# Power.net
KiCad netlist of a schematic drawn in Altium Designer
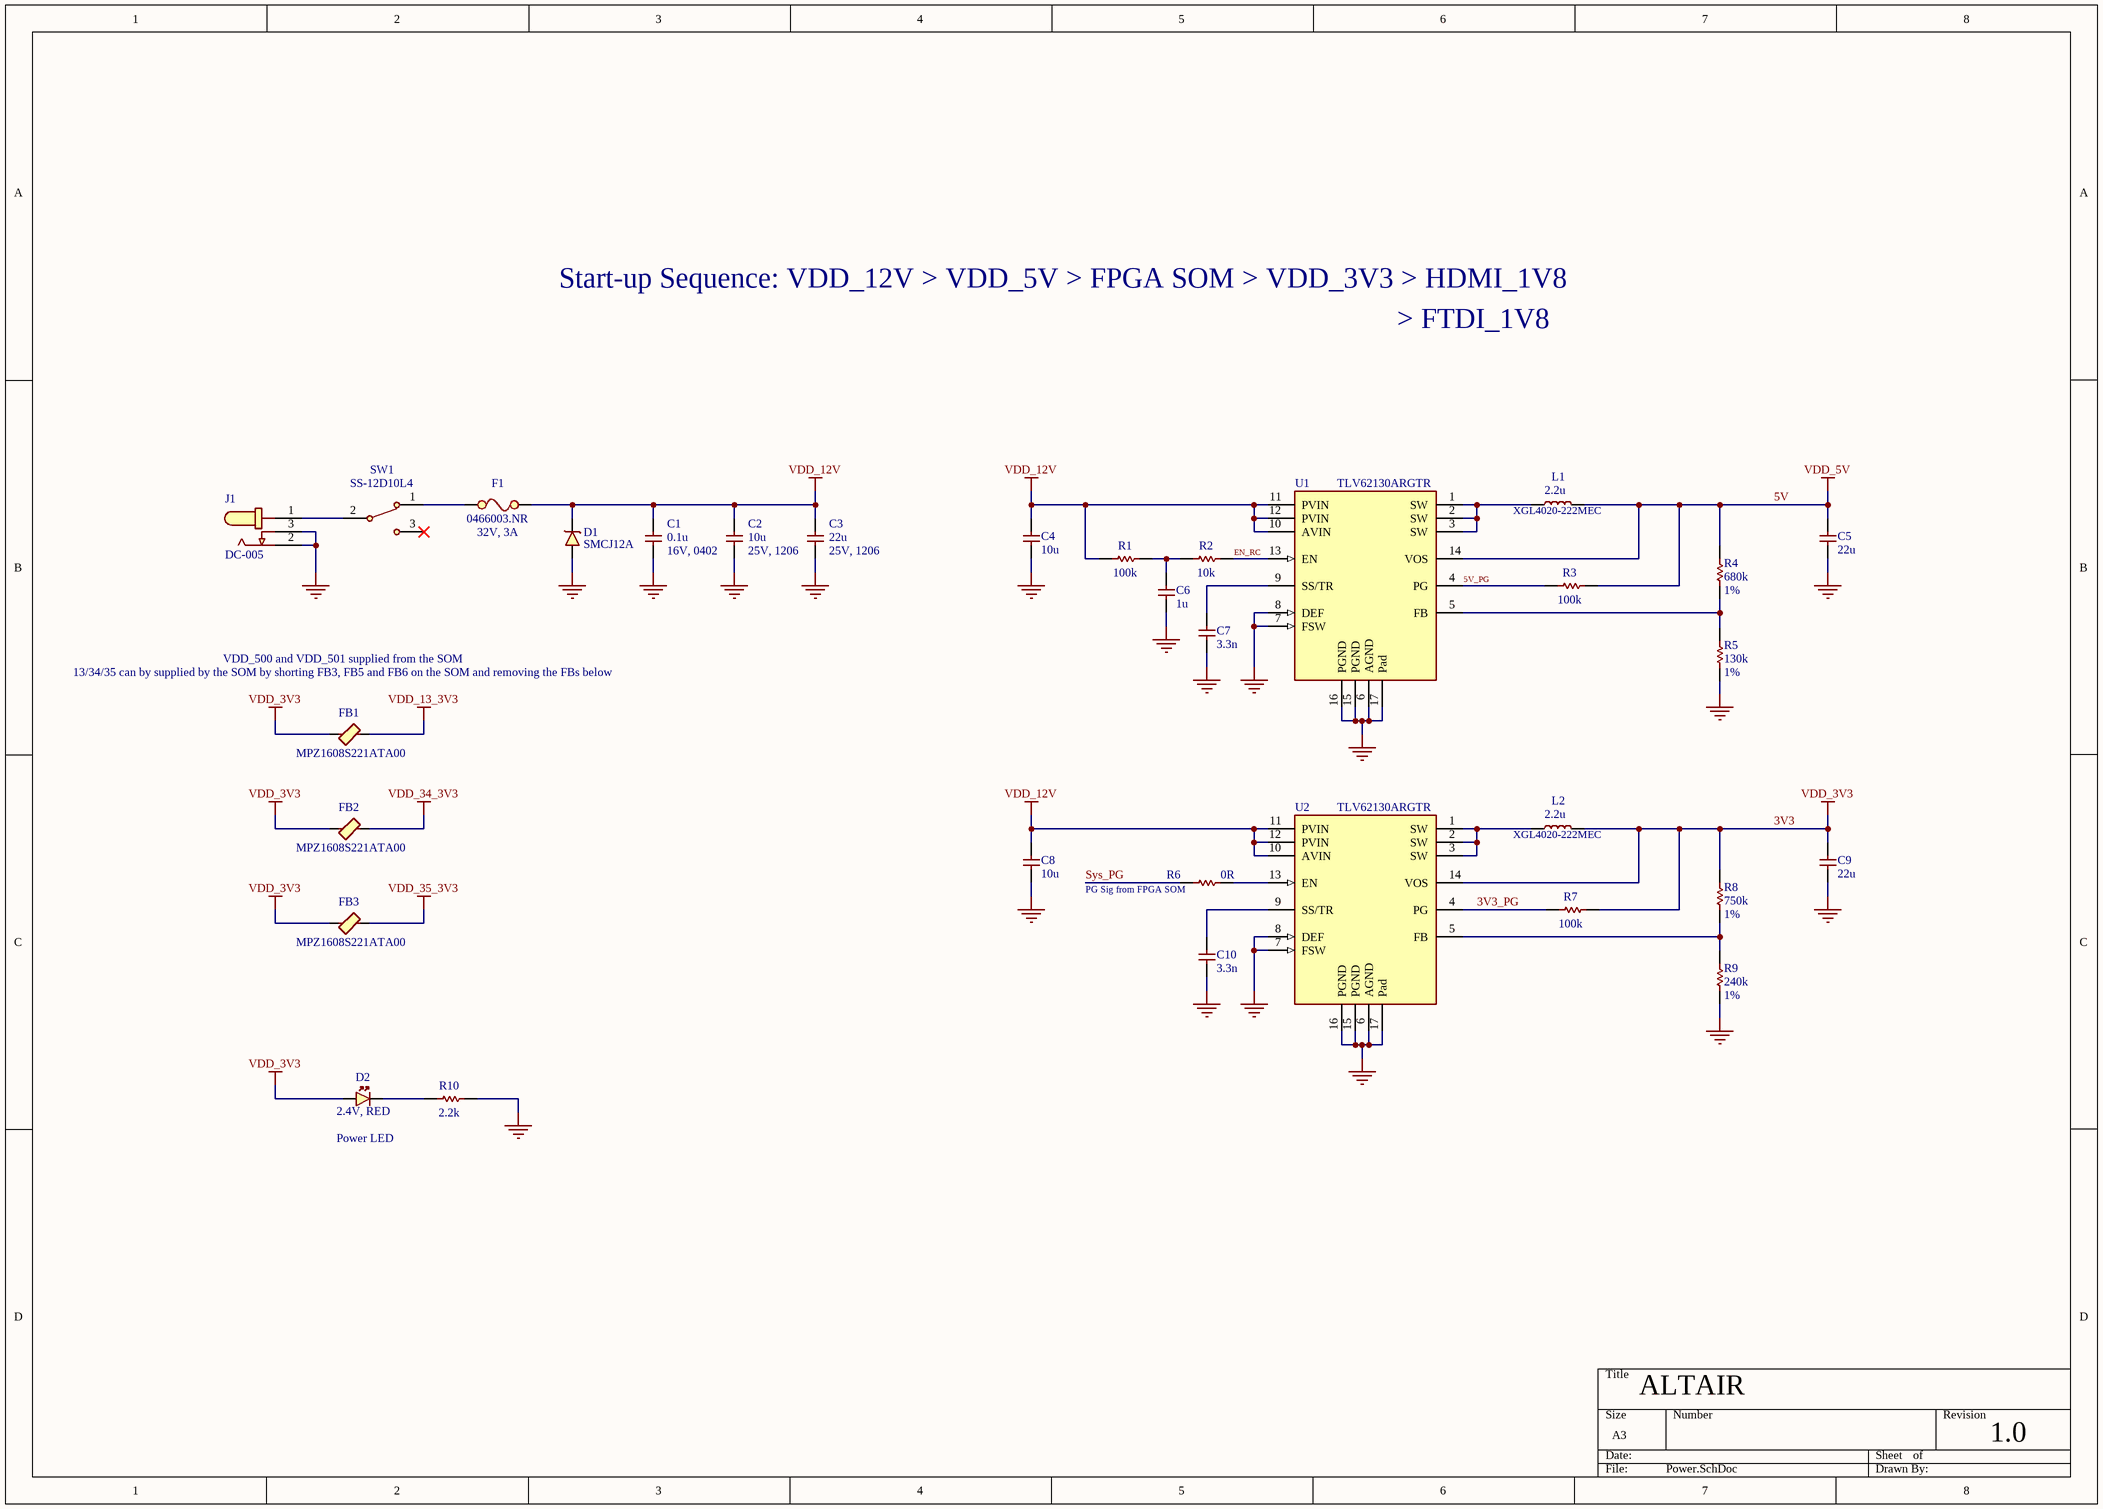
[diagram p0: Power.SchDoc]

(export (version "E")
  (design (tool "Eeschema 10.0.6"))
  (components
    (comp (ref "C1")
      (value "0.1u")
      (footprint "CAP_0402")
      (description "Capacitor SMD 0402")
      (fields
        (field (name "NOTE/MISC") "16V, 0402")
        (field (name "PART NO") "CL05B104KO5NNNC")
        (field (name "JLCPCB PART #") "C338112")
      )
      (libsource (lib "personalGenericLib") (part "CAP_0402"))
    )
    (comp (ref "C2")
      (value "10u")
      (footprint "CAP_1206")
      (description "Capacitor SMD 1206")
      (fields
        (field (name "NOTE/MISC") "25V, 1206")
        (field (name "PART NO") "CL31A106KAHNNNE")
        (field (name "JLCPCB PART #") "C9807")
      )
      (libsource (lib "personalGenericLib") (part "CAP_1206"))
    )
    (comp (ref "C3")
      (value "22u")
      (footprint "CAP_1206")
      (description "Capacitor SMD 1206")
      (fields
        (field (name "NOTE/MISC") "25V, 1206")
        (field (name "PART NO") "CL31A226KAHNNNE")
        (field (name "JLCPCB PART #") "C12891")
      )
      (libsource (lib "personalGenericLib") (part "CAP_1206"))
    )
    (comp (ref "C4")
      (value "10u")
      (footprint "CAP_1206")
      (description "Capacitor SMD 1206")
      (fields (field (name "PART NO") "CL31A106KAHNNNE") (field (name "JLCPCB PART #") "C9807"))
      (libsource (lib "personalGenericLib") (part "CAP_1206"))
    )
    (comp (ref "C5")
      (value "22u")
      (footprint "CAP_1206")
      (description "Capacitor SMD 1206")
      (fields (field (name "PART NO") "CL31A226KAHNNNE") (field (name "JLCPCB PART #") "C12891"))
      (libsource (lib "personalGenericLib") (part "CAP_1206"))
    )
    (comp (ref "C6")
      (value "1u")
      (footprint "CAP_0402")
      (description "Capacitor SMD 0402")
      (fields (field (name "JLCPCB PART #") "C14445") (field (name "PART NO") "CL05A105KP5NNNC"))
      (libsource (lib "personalGenericLib") (part "CAP_0402"))
    )
    (comp (ref "C7")
      (value "3.3n")
      (footprint "CAP_0402")
      (description "Capacitor SMD 0402")
      (fields (field (name "JLCPCB PART #") "C527004") (field (name "PART NO") "CC0402JRX7R8BB332"))
      (libsource (lib "personalGenericLib") (part "CAP_0402"))
    )
    (comp (ref "C8")
      (value "10u")
      (footprint "CAP_1206")
      (description "Capacitor SMD 1206")
      (fields (field (name "PART NO") "CL31A106KAHNNNE") (field (name "JLCPCB PART #") "C9807"))
      (libsource (lib "personalGenericLib") (part "CAP_1206"))
    )
    (comp (ref "C9")
      (value "22u")
      (footprint "CAP_1206")
      (description "Capacitor SMD 1206")
      (fields (field (name "PART NO") "CL31A226KAHNNNE") (field (name "JLCPCB PART #") "C12891"))
      (libsource (lib "personalGenericLib") (part "CAP_1206"))
    )
    (comp (ref "C10")
      (value "3.3n")
      (footprint "CAP_0402")
      (description "Capacitor SMD 0402")
      (fields (field (name "JLCPCB PART #") "C527004") (field (name "PART NO") "CC0402JRX7R8BB332"))
      (libsource (lib "personalGenericLib") (part "CAP_0402"))
    )
    (comp (ref "D1")
      (value "SMCJ12A")
      (footprint "LFUS-DO-214AB-2_V")
      (fields (field (name "JLCPCB PART #") "C224038"))
      (libsource (lib "personalGenericLib") (part "SMCJ12A"))
    )
    (comp (ref "D2")
      (value "RED")
      (footprint "LED_0805_RED")
      (description "LED 0805 RED SMD")
      (fields
        (field (name "JLCPCB PART #") "C497952")
        (field (name "NOTE/MISC") "2.4V, RED")
        (field (name "PART NO") "HL-PSC-2012S9AC")
      )
      (libsource (lib "personalGenericLib") (part "LED_0805_RED"))
    )
    (comp (ref "F1")
      (value "0466003.NR")
      (footprint "0466003.NR")
      (description "FUSE MNT 3A 32VAC/VDC 1206")
      (fields (field (name "JLCPCB PART #") "C14165") (field (name "NOTE/MISC") "32V, 3A"))
      (libsource (lib "personalGenericLib") (part "0466003.NR"))
    )
    (comp (ref "FB1")
      (value "220")
      (footprint "BEADC1608X75N")
      (description "Ferrite Bead")
      (fields (field (name "PART NO") "MPZ1608S221ATA00") (field (name "JLCPCB PART #") "C76815"))
      (libsource (lib "personalGenericLib") (part "MPZ1608S221ATA00"))
    )
    (comp (ref "FB2")
      (value "220")
      (footprint "BEADC1608X75N")
      (description "Ferrite Bead")
      (fields (field (name "PART NO") "MPZ1608S221ATA00") (field (name "JLCPCB PART #") "C76815"))
      (libsource (lib "personalGenericLib") (part "MPZ1608S221ATA00"))
    )
    (comp (ref "FB3")
      (value "220")
      (footprint "BEADC1608X75N")
      (description "Ferrite Bead")
      (fields (field (name "PART NO") "MPZ1608S221ATA00") (field (name "JLCPCB PART #") "C76815"))
      (libsource (lib "personalGenericLib") (part "MPZ1608S221ATA00"))
    )
    (comp (ref "J1")
      (value "DC-005")
      (footprint "DC-005-A200")
      (description "DC Jack")
      (fields (field (name "JLCPCB PART #") "C720557"))
      (libsource (lib "personalGenericLib") (part "DC-005"))
    )
    (comp (ref "L1")
      (value "2.2u")
      (footprint "personalGenericFootprintLib:XGL4020222MEC")
      (description "Inductor SMD 2.2 uH")
      (fields
        (field (name "NOTE/MISC") "XGL4020-222MEC")
        (field (name "PART NO") "XGL4020-222MEC")
        (field (name "JLCPCB PART #") "C6012410")
      )
      (libsource (lib "personalGenericLib") (part "IND_XGL4020-222MEC"))
    )
    (comp (ref "L2")
      (value "2.2u")
      (footprint "personalGenericFootprintLib:XGL4020222MEC")
      (description "Inductor SMD 2.2 uH")
      (fields
        (field (name "NOTE/MISC") "XGL4020-222MEC")
        (field (name "PART NO") "XGL4020-222MEC")
        (field (name "JLCPCB PART #") "C6012410")
      )
      (libsource (lib "personalGenericLib") (part "IND_XGL4020-222MEC"))
    )
    (comp (ref "R1")
      (value "100k")
      (footprint "RES_0402")
      (description "Resistor SMD 0402")
      (fields (field (name "JLCPCB PART #") "C106234") (field (name "PART NO") "RC0402JR-07100KL"))
      (libsource (lib "personalGenericLib") (part "RES_0402"))
    )
    (comp (ref "R2")
      (value "10k")
      (footprint "RES_0402")
      (description "Resistor SMD 0402")
      (fields (field (name "JLCPCB PART #") "C60489") (field (name "PART NO") "RC0402JR-0710KL"))
      (libsource (lib "personalGenericLib") (part "RES_0402"))
    )
    (comp (ref "R3")
      (value "100k")
      (footprint "RES_0402")
      (description "Resistor SMD 0402")
      (fields (field (name "JLCPCB PART #") "C106234") (field (name "PART NO") "RC0402JR-07100KL"))
      (libsource (lib "personalGenericLib") (part "RES_0402"))
    )
    (comp (ref "R4")
      (value "680k")
      (footprint "RES_0402")
      (description "Resistor SMD 0402")
      (fields
        (field (name "JLCPCB PART #") "C163456")
        (field (name "NOTE/MISC") "1%")
        (field (name "PART NO") "RC0402FR-07680KL")
      )
      (libsource (lib "personalGenericLib") (part "RES_0402"))
    )
    (comp (ref "R5")
      (value "130k")
      (footprint "RES_0402")
      (description "Resistor SMD 0402")
      (fields
        (field (name "JLCPCB PART #") "C93946")
        (field (name "NOTE/MISC") "1%")
        (field (name "PART NO") "RC0402FR-07130KL")
      )
      (libsource (lib "personalGenericLib") (part "RES_0402"))
    )
    (comp (ref "R6")
      (value "0R")
      (footprint "RES_0402")
      (description "Resistor SMD 0402")
      (fields (field (name "JLCPCB PART #") "C60485") (field (name "PART NO") "RC0402JR-070RL"))
      (libsource (lib "personalGenericLib") (part "RES_0402"))
    )
    (comp (ref "R7")
      (value "100k")
      (footprint "RES_0402")
      (description "Resistor SMD 0402")
      (fields (field (name "JLCPCB PART #") "C106234") (field (name "PART NO") "RC0402JR-07100KL"))
      (libsource (lib "personalGenericLib") (part "RES_0402"))
    )
    (comp (ref "R8")
      (value "750k")
      (footprint "RES_0402")
      (description "Resistor SMD 0402")
      (fields
        (field (name "JLCPCB PART #") "C137937")
        (field (name "NOTE/MISC") "1%")
        (field (name "PART NO") "RC0402FR-07750KL")
      )
      (libsource (lib "personalGenericLib") (part "RES_0402"))
    )
    (comp (ref "R9")
      (value "240k")
      (footprint "RES_0402")
      (description "Resistor SMD 0402")
      (fields
        (field (name "JLCPCB PART #") "C138029")
        (field (name "NOTE/MISC") "1%")
        (field (name "PART NO") "RC0402FR-07240KL")
      )
      (libsource (lib "personalGenericLib") (part "RES_0402"))
    )
    (comp (ref "R10")
      (value "2.2k")
      (footprint "RES_0402")
      (description "Resistor SMD 0402")
      (fields (field (name "JLCPCB PART #") "C163447") (field (name "PART NO") "RC0402JR-072K2L"))
      (libsource (lib "personalGenericLib") (part "RES_0402"))
    )
    (comp (ref "SW1")
      (value "SS-12D10L4")
      (footprint "SS-12D10L5")
      (description "Slide Switch")
      (fields (field (name "JLCPCB PART #") "C843364"))
      (libsource (lib "personalGenericLib") (part "SS-12D10L5"))
    )
    (comp (ref "U1")
      (value "TLV62130ARGTR")
      (footprint "FP-RGT0016C-MFG")
      (description "IC REG BUCK ADJUSTABLE 3A 16QFN")
      (fields (field (name "JLCPCB PART #") "C138520"))
      (libsource (lib "personalGenericLib") (part "TLV62130ARGTR"))
    )
    (comp (ref "U2")
      (value "TLV62130ARGTR")
      (footprint "FP-RGT0016C-MFG")
      (description "IC REG BUCK ADJUSTABLE 3A 16QFN")
      (fields (field (name "JLCPCB PART #") "C138520"))
      (libsource (lib "personalGenericLib") (part "TLV62130ARGTR"))
    )
  )
  (nets
    (net (code "1") (name "/3V3_PG") (class "Default")
      (node (ref "R7") (pin "1") (pinfunction "1_1") (pintype "passive"))
      (node (ref "U2") (pin "4") (pinfunction "PG_4") (pintype "open_collector"))
    )
    (net (code "2") (name "/5V_PG") (class "Default")
      (node (ref "R3") (pin "1") (pinfunction "1_1") (pintype "passive"))
      (node (ref "U1") (pin "4") (pinfunction "PG_4") (pintype "open_collector"))
    )
    (net (code "3") (name "/EN_RC") (class "Default")
      (node (ref "R2") (pin "1") (pinfunction "1_1") (pintype "passive"))
      (node (ref "U1") (pin "13") (pinfunction "EN_13") (pintype "input"))
    )
    (net (code "4") (name "/Sys_PG") (class "Default")
      (node (ref "R6") (pin "1") (pinfunction "1_1") (pintype "passive"))
    )
    (net (code "5") (name "GND") (class "Default")
      (node (ref "C1") (pin "1") (pinfunction "1_1") (pintype "passive"))
      (node (ref "C10") (pin "1") (pinfunction "1_1") (pintype "passive"))
      (node (ref "C2") (pin "1") (pinfunction "1_1") (pintype "passive"))
      (node (ref "C3") (pin "1") (pinfunction "1_1") (pintype "passive"))
      (node (ref "C4") (pin "1") (pinfunction "1_1") (pintype "passive"))
      (node (ref "C5") (pin "1") (pinfunction "1_1") (pintype "passive"))
      (node (ref "C6") (pin "1") (pinfunction "1_1") (pintype "passive"))
      (node (ref "C7") (pin "1") (pinfunction "1_1") (pintype "passive"))
      (node (ref "C8") (pin "1") (pinfunction "1_1") (pintype "passive"))
      (node (ref "C9") (pin "1") (pinfunction "1_1") (pintype "passive"))
      (node (ref "D1") (pin "2") (pinfunction "2_2") (pintype "passive"))
      (node (ref "J1") (pin "2") (pinfunction "2_2") (pintype "passive"))
      (node (ref "J1") (pin "3") (pinfunction "3_3") (pintype "passive"))
      (node (ref "R10") (pin "2") (pinfunction "2_2") (pintype "passive"))
      (node (ref "R5") (pin "2") (pinfunction "2_2") (pintype "passive"))
      (node (ref "R9") (pin "2") (pinfunction "2_2") (pintype "passive"))
      (node (ref "U1") (pin "15") (pinfunction "PGND_15") (pintype "power_in"))
      (node (ref "U1") (pin "16") (pinfunction "PGND_16") (pintype "power_in"))
      (node (ref "U1") (pin "17") (pinfunction "Pad_17") (pintype "power_in"))
      (node (ref "U1") (pin "6") (pinfunction "AGND_6") (pintype "power_in"))
      (node (ref "U1") (pin "7") (pinfunction "FSW_7") (pintype "input"))
      (node (ref "U1") (pin "8") (pinfunction "DEF_8") (pintype "input"))
      (node (ref "U2") (pin "15") (pinfunction "PGND_15") (pintype "power_in"))
      (node (ref "U2") (pin "16") (pinfunction "PGND_16") (pintype "power_in"))
      (node (ref "U2") (pin "17") (pinfunction "Pad_17") (pintype "power_in"))
      (node (ref "U2") (pin "6") (pinfunction "AGND_6") (pintype "power_in"))
      (node (ref "U2") (pin "7") (pinfunction "FSW_7") (pintype "input"))
      (node (ref "U2") (pin "8") (pinfunction "DEF_8") (pintype "input"))
    )
    (net (code "6") (name "Net-(C6-Pad2)") (class "Default")
      (node (ref "C6") (pin "2") (pinfunction "2_2") (pintype "passive"))
      (node (ref "R1") (pin "1") (pinfunction "1_1") (pintype "passive"))
      (node (ref "R2") (pin "2") (pinfunction "2_2") (pintype "passive"))
    )
    (net (code "7") (name "Net-(D2-PadK)") (class "Default")
      (node (ref "D2") (pin "K") (pinfunction "K_K") (pintype "passive"))
      (node (ref "R10") (pin "1") (pinfunction "1_1") (pintype "passive"))
    )
    (net (code "8") (name "Net-(F1-Pad1)") (class "Default")
      (node (ref "F1") (pin "1") (pinfunction "1_1") (pintype "passive"))
      (node (ref "SW1") (pin "1") (pinfunction "1_1") (pintype "passive"))
    )
    (net (code "9") (name "Net-(L1-Pad1)") (class "Default")
      (node (ref "L1") (pin "1") (pinfunction "1_1") (pintype "passive"))
      (node (ref "U1") (pin "1") (pinfunction "SW_1") (pintype "passive"))
      (node (ref "U1") (pin "2") (pinfunction "SW_2") (pintype "passive"))
      (node (ref "U1") (pin "3") (pinfunction "SW_3") (pintype "passive"))
    )
    (net (code "10") (name "Net-(L2-Pad1)") (class "Default")
      (node (ref "L2") (pin "1") (pinfunction "1_1") (pintype "passive"))
      (node (ref "U2") (pin "1") (pinfunction "SW_1") (pintype "passive"))
      (node (ref "U2") (pin "2") (pinfunction "SW_2") (pintype "passive"))
      (node (ref "U2") (pin "3") (pinfunction "SW_3") (pintype "passive"))
    )
    (net (code "11") (name "Net-(SW1-C)") (class "Default")
      (node (ref "J1") (pin "1") (pinfunction "1_1") (pintype "passive"))
      (node (ref "SW1") (pin "2") (pinfunction "C_2") (pintype "passive"))
    )
    (net (code "12") (name "Net-(U1-FB)") (class "Default")
      (node (ref "R4") (pin "1") (pinfunction "1_1") (pintype "passive"))
      (node (ref "R5") (pin "1") (pinfunction "1_1") (pintype "passive"))
      (node (ref "U1") (pin "5") (pinfunction "FB_5") (pintype "passive"))
    )
    (net (code "13") (name "Net-(U1-SS{slash}TR)") (class "Default")
      (node (ref "C7") (pin "2") (pinfunction "2_2") (pintype "passive"))
      (node (ref "U1") (pin "9") (pinfunction "SS/TR_9") (pintype "passive"))
    )
    (net (code "14") (name "Net-(U2-EN)") (class "Default")
      (node (ref "R6") (pin "2") (pinfunction "2_2") (pintype "passive"))
      (node (ref "U2") (pin "13") (pinfunction "EN_13") (pintype "input"))
    )
    (net (code "15") (name "Net-(U2-FB)") (class "Default")
      (node (ref "R8") (pin "1") (pinfunction "1_1") (pintype "passive"))
      (node (ref "R9") (pin "1") (pinfunction "1_1") (pintype "passive"))
      (node (ref "U2") (pin "5") (pinfunction "FB_5") (pintype "passive"))
    )
    (net (code "16") (name "Net-(U2-SS{slash}TR)") (class "Default")
      (node (ref "C10") (pin "2") (pinfunction "2_2") (pintype "passive"))
      (node (ref "U2") (pin "9") (pinfunction "SS/TR_9") (pintype "passive"))
    )
    (net (code "17") (name "VDD_3V3") (class "Default")
      (node (ref "C9") (pin "2") (pinfunction "2_2") (pintype "passive"))
      (node (ref "D2") (pin "A") (pinfunction "A_A") (pintype "passive"))
      (node (ref "FB1") (pin "1") (pinfunction "1_1") (pintype "passive"))
      (node (ref "FB2") (pin "1") (pinfunction "1_1") (pintype "passive"))
      (node (ref "FB3") (pin "1") (pinfunction "1_1") (pintype "passive"))
      (node (ref "L2") (pin "2") (pinfunction "2_2") (pintype "passive"))
      (node (ref "R7") (pin "2") (pinfunction "2_2") (pintype "passive"))
      (node (ref "R8") (pin "2") (pinfunction "2_2") (pintype "passive"))
      (node (ref "U2") (pin "14") (pinfunction "VOS_14") (pintype "passive"))
    )
    (net (code "18") (name "VDD_5V") (class "Default")
      (node (ref "C5") (pin "2") (pinfunction "2_2") (pintype "passive"))
      (node (ref "L1") (pin "2") (pinfunction "2_2") (pintype "passive"))
      (node (ref "R3") (pin "2") (pinfunction "2_2") (pintype "passive"))
      (node (ref "R4") (pin "2") (pinfunction "2_2") (pintype "passive"))
      (node (ref "U1") (pin "14") (pinfunction "VOS_14") (pintype "passive"))
    )
    (net (code "19") (name "VDD_12V") (class "Default")
      (node (ref "C1") (pin "2") (pinfunction "2_2") (pintype "passive"))
      (node (ref "C2") (pin "2") (pinfunction "2_2") (pintype "passive"))
      (node (ref "C3") (pin "2") (pinfunction "2_2") (pintype "passive"))
      (node (ref "C4") (pin "2") (pinfunction "2_2") (pintype "passive"))
      (node (ref "C8") (pin "2") (pinfunction "2_2") (pintype "passive"))
      (node (ref "D1") (pin "1") (pinfunction "1_1") (pintype "passive"))
      (node (ref "F1") (pin "2") (pinfunction "2_2") (pintype "passive"))
      (node (ref "R1") (pin "2") (pinfunction "2_2") (pintype "passive"))
      (node (ref "U1") (pin "10") (pinfunction "AVIN_10") (pintype "power_in"))
      (node (ref "U1") (pin "11") (pinfunction "PVIN_11") (pintype "power_in"))
      (node (ref "U1") (pin "12") (pinfunction "PVIN_12") (pintype "power_in"))
      (node (ref "U2") (pin "10") (pinfunction "AVIN_10") (pintype "power_in"))
      (node (ref "U2") (pin "11") (pinfunction "PVIN_11") (pintype "power_in"))
      (node (ref "U2") (pin "12") (pinfunction "PVIN_12") (pintype "power_in"))
    )
    (net (code "20") (name "VDD_13_3V3") (class "Default")
      (node (ref "FB1") (pin "2") (pinfunction "2_2") (pintype "passive"))
    )
    (net (code "21") (name "VDD_34_3V3") (class "Default")
      (node (ref "FB2") (pin "2") (pinfunction "2_2") (pintype "passive"))
    )
    (net (code "22") (name "VDD_35_3V3") (class "Default")
      (node (ref "FB3") (pin "2") (pinfunction "2_2") (pintype "passive"))
    )
    (net (code "23") (name "unconnected-(SW1-Pad3)") (class "Default")
      (node (ref "SW1") (pin "3") (pinfunction "3_3") (pintype "passive+no_connect"))
    )
  )
)
